# Main.net
KiCad netlist of a schematic drawn in Altium Designer
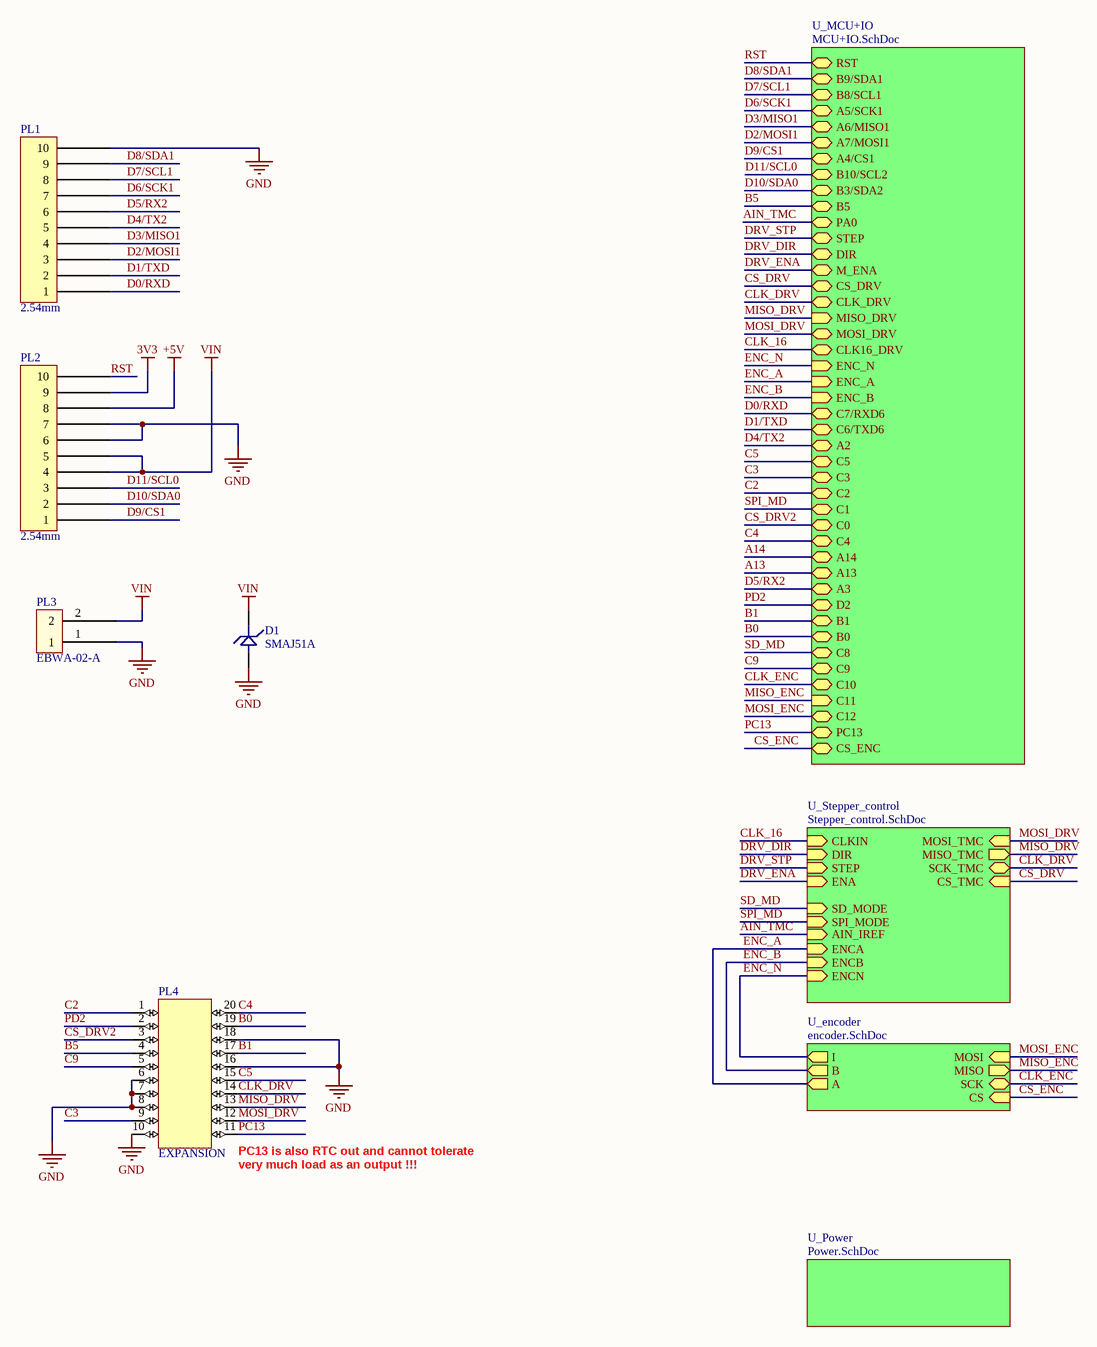
[diagram p0: Main.SchDoc]

(export (version "E")
  (design (tool "Eeschema 10.0.6"))
  (components
    (comp (ref "D1")
      (value "SMAJ51A")
      (footprint "DIOM4227X23N")
      (description "Diode TVS Single Uni-Dir 51V 400W 2-Pin SMA")
      (libsource (lib "ON Development Vault") (part "SZBZX84C Zener"))
    )
    (comp (ref "PL1")
      (value "2.54mm")
      (footprint "10-pin female 2.54mm")
      (description "Pin header 10-pin 2.54mm female")
      (fields (field (name "MFG. PART NUMBER") "DS1023-1*10S21"))
      (libsource (lib "ON Development Vault") (part "10-pin header"))
    )
    (comp (ref "PL2")
      (value "2.54mm")
      (footprint "10-pin female 2.54mm")
      (description "Pin header 10-pin 2.54mm female")
      (fields (field (name "MFG. PART NUMBER") "DS1023-1*10S21"))
      (libsource (lib "ON Development Vault") (part "10-pin header"))
    )
    (comp (ref "PL3")
      (value "EBWA-02-A")
      (footprint "691214110002")
      (libsource (lib "ON Development Vault") (part "Header 2-way"))
    )
    (comp (ref "PL4")
      (value "EXPANSION")
      (footprint "20021121-00020T4LF-Footprint-1")
      (description "Conn Unshrouded Header HDR 20 POS 1.27mm Solder ST Top Entry SMD Tube")
      (libsource (lib "ON Development Vault") (part "20021121-00020T4LF-Symbol-1"))
    )
  )
  (nets
    (net (code "1") (name "+5V") (class "Default")
      (node (ref "PL2") (pin "8") (pinfunction "8_8") (pintype "passive"))
    )
    (net (code "5") (name "/B0") (class "Default") (node (ref "PL4") (pin "19") (pintype "bidirectional")))
    (net (code "6") (name "/B1") (class "Default") (node (ref "PL4") (pin "17") (pintype "bidirectional")))
    (net (code "7") (name "/B5") (class "Default") (node (ref "PL4") (pin "4") (pintype "bidirectional")))
    (net (code "8") (name "/C2") (class "Default") (node (ref "PL4") (pin "1") (pintype "bidirectional")))
    (net (code "9") (name "/C3") (class "Default") (node (ref "PL4") (pin "9") (pintype "bidirectional")))
    (net (code "10") (name "/C4") (class "Default") (node (ref "PL4") (pin "20") (pintype "bidirectional")))
    (net (code "11") (name "/C5") (class "Default") (node (ref "PL4") (pin "15") (pintype "bidirectional")))
    (net (code "12") (name "/C9") (class "Default") (node (ref "PL4") (pin "5") (pintype "bidirectional")))
    (net (code "14") (name "/CLK_DRV") (class "Default")
      (node (ref "PL4") (pin "14") (pintype "bidirectional"))
    )
    (net (code "17") (name "/CS_DRV2") (class "Default")
      (node (ref "PL4") (pin "3") (pintype "bidirectional"))
    )
    (net (code "19") (name "/D0{slash}RXD") (class "Default")
      (node (ref "PL1") (pin "1") (pinfunction "1_1") (pintype "passive"))
    )
    (net (code "20") (name "/D1{slash}TXD") (class "Default")
      (node (ref "PL1") (pin "2") (pinfunction "2_2") (pintype "passive"))
    )
    (net (code "21") (name "/D2{slash}MOSI1") (class "Default")
      (node (ref "PL1") (pin "3") (pinfunction "3_3") (pintype "passive"))
    )
    (net (code "22") (name "/D3{slash}MISO1") (class "Default")
      (node (ref "PL1") (pin "4") (pinfunction "4_4") (pintype "passive"))
    )
    (net (code "23") (name "/D4{slash}TX2") (class "Default")
      (node (ref "PL1") (pin "5") (pinfunction "5_5") (pintype "passive"))
    )
    (net (code "24") (name "/D5{slash}RX2") (class "Default")
      (node (ref "PL1") (pin "6") (pinfunction "6_6") (pintype "passive"))
    )
    (net (code "25") (name "/D6{slash}SCK1") (class "Default")
      (node (ref "PL1") (pin "7") (pinfunction "7_7") (pintype "passive"))
    )
    (net (code "26") (name "/D7{slash}SCL1") (class "Default")
      (node (ref "PL1") (pin "8") (pinfunction "8_8") (pintype "passive"))
    )
    (net (code "27") (name "/D8{slash}SDA1") (class "Default")
      (node (ref "PL1") (pin "9") (pinfunction "9_9") (pintype "passive"))
    )
    (net (code "28") (name "/D9{slash}CS1") (class "Default")
      (node (ref "PL2") (pin "1") (pinfunction "1_1") (pintype "passive"))
    )
    (net (code "29") (name "/D10{slash}SDA0") (class "Default")
      (node (ref "PL2") (pin "2") (pinfunction "2_2") (pintype "passive"))
    )
    (net (code "30") (name "/D11{slash}SCL0") (class "Default")
      (node (ref "PL2") (pin "3") (pinfunction "3_3") (pintype "passive"))
    )
    (net (code "37") (name "/MISO_DRV") (class "Default")
      (node (ref "PL4") (pin "13") (pintype "bidirectional"))
    )
    (net (code "39") (name "/MOSI_DRV") (class "Default")
      (node (ref "PL4") (pin "12") (pintype "bidirectional"))
    )
    (net (code "41") (name "/PC13") (class "Default") (node (ref "PL4") (pin "11") (pintype "bidirectional")))
    (net (code "42") (name "/PD2") (class "Default") (node (ref "PL4") (pin "2") (pintype "bidirectional")))
    (net (code "43") (name "/RST") (class "Default")
      (node (ref "PL2") (pin "10") (pinfunction "10_10") (pintype "passive"))
    )
    (net (code "46") (name "3V3") (class "Default")
      (node (ref "PL2") (pin "9") (pinfunction "9_9") (pintype "passive"))
    )
    (net (code "47") (name "GND") (class "Default")
      (node (ref "D1") (pin "1") (pinfunction "1_1") (pintype "passive"))
      (node (ref "PL1") (pin "10") (pinfunction "10_10") (pintype "passive"))
      (node (ref "PL2") (pin "6") (pinfunction "6_6") (pintype "passive"))
      (node (ref "PL2") (pin "7") (pinfunction "7_7") (pintype "passive"))
      (node (ref "PL3") (pin "1") (pinfunction "1_1") (pintype "passive"))
      (node (ref "PL4") (pin "10") (pintype "bidirectional"))
      (node (ref "PL4") (pin "16") (pintype "bidirectional"))
      (node (ref "PL4") (pin "18") (pintype "bidirectional"))
      (node (ref "PL4") (pin "6") (pintype "bidirectional"))
      (node (ref "PL4") (pin "7") (pintype "bidirectional"))
      (node (ref "PL4") (pin "8") (pintype "bidirectional"))
    )
    (net (code "48") (name "VIN") (class "Default")
      (node (ref "D1") (pin "3") (pinfunction "3_3") (pintype "passive"))
      (node (ref "PL2") (pin "4") (pinfunction "4_4") (pintype "passive"))
      (node (ref "PL2") (pin "5") (pinfunction "5_5") (pintype "passive"))
      (node (ref "PL3") (pin "2") (pinfunction "2_2") (pintype "passive"))
    )
  )
)
